# temperature_sensor.net
KiCad netlist of a schematic drawn in EAGLE
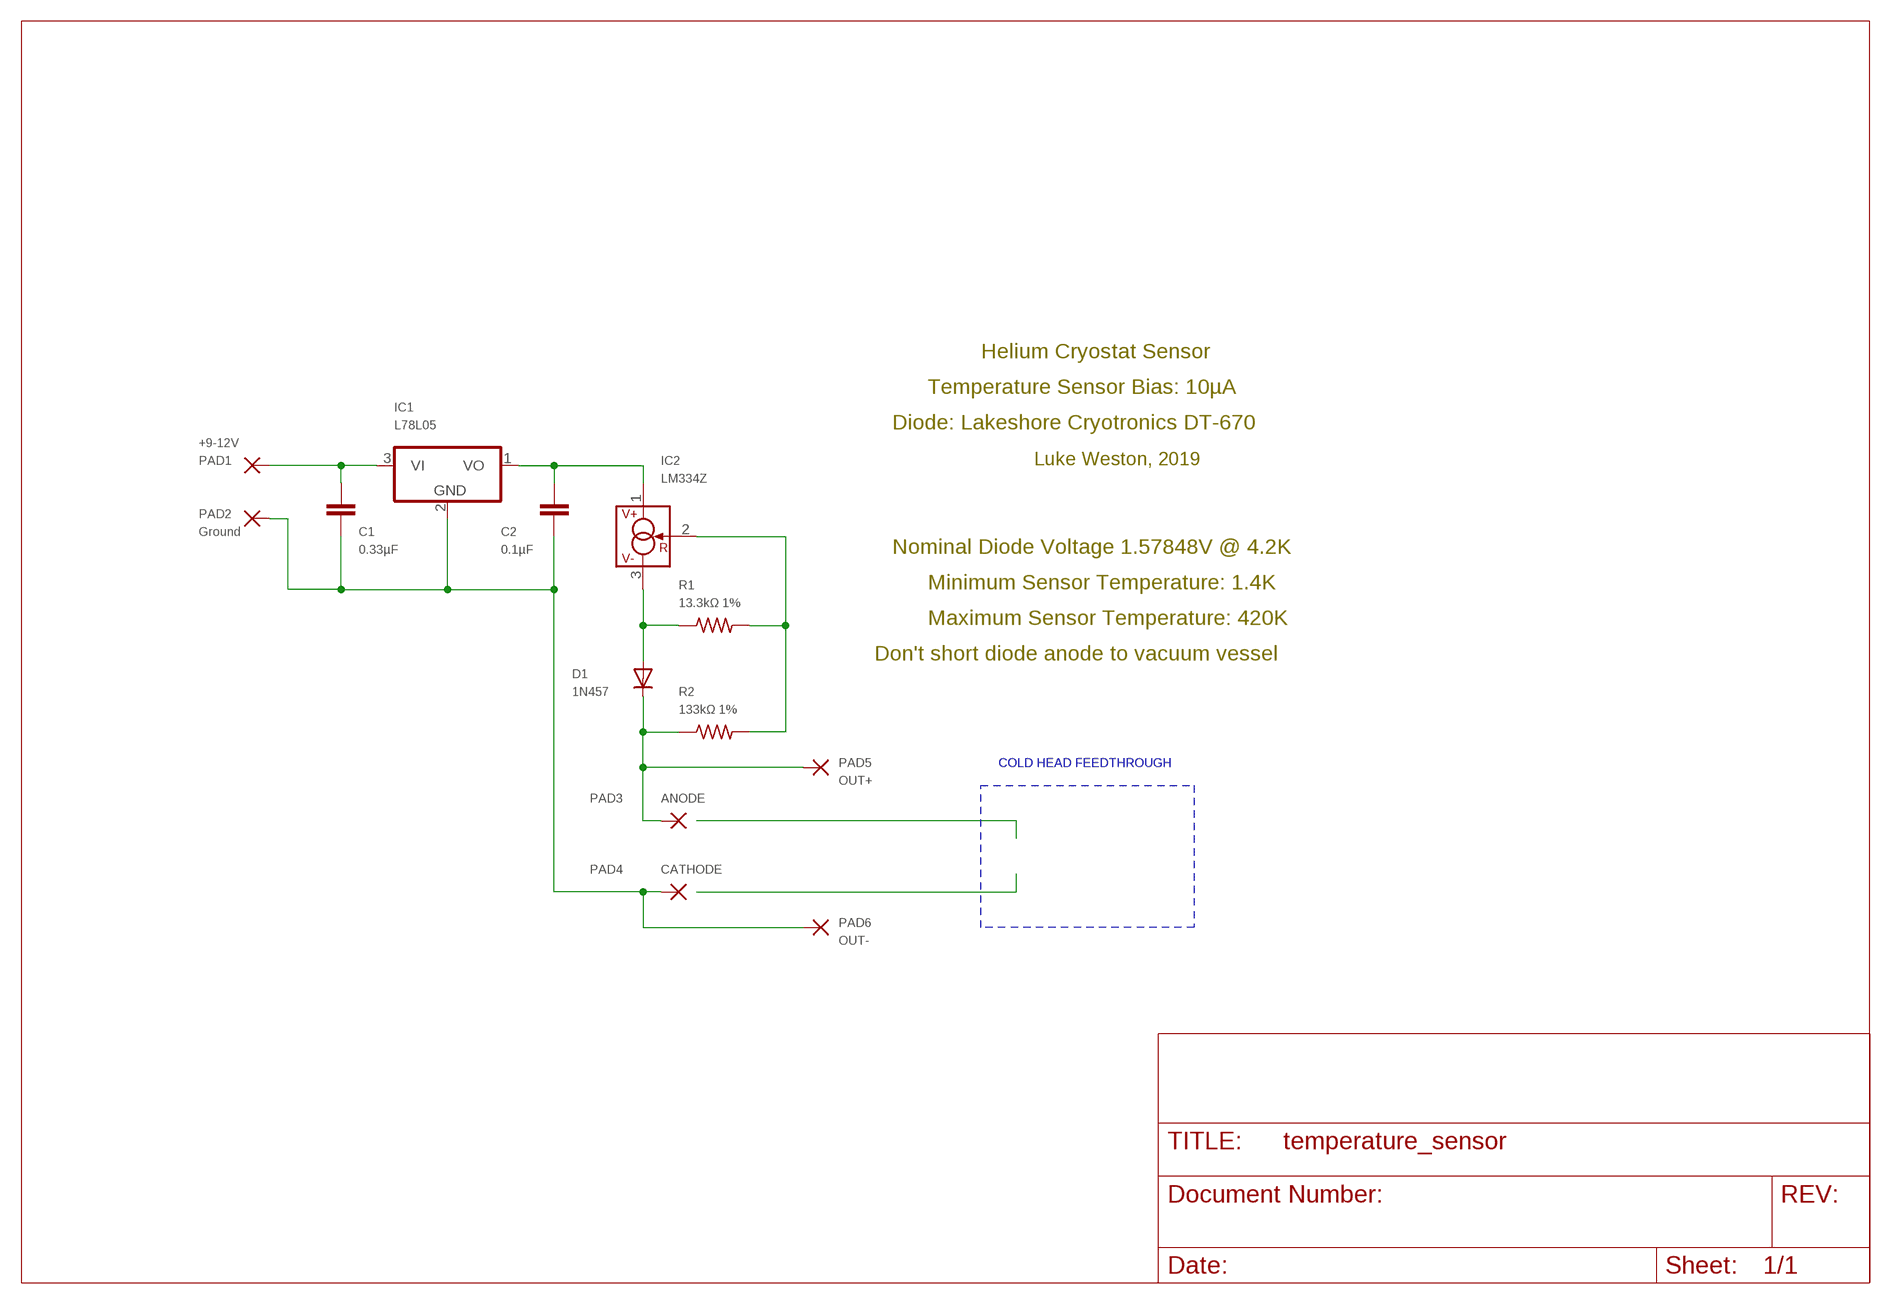
[diagram p0: schematic, sheet 1]

(export (version "E")
  (design (tool "Eeschema 10.0.6"))
  (components
    (comp (ref "C1")
      (value "0.33µF")
      (footprint "eagle-import:C050-024X044")
      (libsource (lib "eagle-import") (part "C-EU050-024X044"))
    )
    (comp (ref "C2")
      (value "0.1µF")
      (footprint "eagle-import:C050-024X044")
      (libsource (lib "eagle-import") (part "C-EU050-024X044"))
    )
    (comp (ref "D1")
      (value "1N457")
      (footprint "eagle-import:DO41-10")
      (libsource (lib "eagle-import") (part "1N4004"))
    )
    (comp (ref "IC1")
      (value "L78L05")
      (footprint "eagle-import:TO92")
      (libsource (lib "eagle-import") (part "78ZL05"))
    )
    (comp (ref "IC2")
      (value "LM334Z")
      (footprint "eagle-import:TO92")
      (libsource (lib "eagle-import") (part "LM34Z3"))
    )
    (comp (ref "PAD1")
      (value "+9-12V")
      (footprint "eagle-import:2,54_1,0")
      (libsource (lib "eagle-import") (part "2,54/1,0"))
    )
    (comp (ref "PAD2")
      (value "Ground")
      (footprint "eagle-import:2,54_1,0")
      (libsource (lib "eagle-import") (part "2,54/1,0"))
    )
    (comp (ref "PAD3")
      (value "ANODE")
      (footprint "eagle-import:2,54_1,0")
      (libsource (lib "eagle-import") (part "2,54/1,0"))
    )
    (comp (ref "PAD4")
      (value "CATHODE")
      (footprint "eagle-import:2,54_1,0")
      (libsource (lib "eagle-import") (part "2,54/1,0"))
    )
    (comp (ref "PAD5")
      (value "OUT+")
      (footprint "eagle-import:2,54_1,0")
      (libsource (lib "eagle-import") (part "2,54/1,0"))
    )
    (comp (ref "PAD6")
      (value "OUT-")
      (footprint "eagle-import:2,54_1,0")
      (libsource (lib "eagle-import") (part "2,54/1,0"))
    )
    (comp (ref "R1")
      (value "13.3kΩ 1%")
      (footprint "eagle-import:0207_10")
      (libsource (lib "eagle-import") (part "R-US_0207/10"))
    )
    (comp (ref "R2")
      (value "133kΩ 1%")
      (footprint "eagle-import:0207_10")
      (libsource (lib "eagle-import") (part "R-US_0207/10"))
    )
  )
  (nets
    (net (code "1") (name "Net-(IC1-GND)") (class "Default")
      (node (ref "C1") (pin "2") (pinfunction "2_2") (pintype "passive"))
      (node (ref "C2") (pin "2") (pinfunction "2_2") (pintype "passive"))
      (node (ref "IC1") (pin "2") (pinfunction "GND_2") (pintype "passive"))
      (node (ref "PAD2") (pin "1") (pinfunction "P_1") (pintype "passive"))
      (node (ref "PAD4") (pin "1") (pinfunction "P_1") (pintype "passive"))
      (node (ref "PAD6") (pin "1") (pinfunction "P_1") (pintype "passive"))
    )
    (net (code "2") (name "Net-(IC1-VI)") (class "Default")
      (node (ref "C1") (pin "1") (pinfunction "1_1") (pintype "passive"))
      (node (ref "IC1") (pin "3") (pinfunction "VI_3") (pintype "input"))
      (node (ref "PAD1") (pin "1") (pinfunction "P_1") (pintype "passive"))
    )
    (net (code "3") (name "Net-(IC1-VO)") (class "Default")
      (node (ref "C2") (pin "1") (pinfunction "1_1") (pintype "passive"))
      (node (ref "IC1") (pin "1") (pinfunction "VO_1") (pintype "passive"))
      (node (ref "IC2") (pin "1") (pinfunction "V+_1") (pintype "passive"))
    )
    (net (code "4") (name "Net-(IC2-R)") (class "Default")
      (node (ref "IC2") (pin "2") (pinfunction "R_2") (pintype "passive"))
      (node (ref "R1") (pin "2") (pinfunction "2_2") (pintype "passive"))
      (node (ref "R2") (pin "2") (pinfunction "2_2") (pintype "passive"))
    )
    (net (code "5") (name "Net-(IC2-V-)") (class "Default")
      (node (ref "D1") (pin "A") (pinfunction "A_A") (pintype "passive"))
      (node (ref "IC2") (pin "3") (pinfunction "V-_3") (pintype "passive"))
      (node (ref "R1") (pin "1") (pinfunction "1_1") (pintype "passive"))
    )
    (net (code "6") (name "Net-(PAD3-P)") (class "Default")
      (node (ref "D1") (pin "C") (pinfunction "C_C") (pintype "passive"))
      (node (ref "PAD3") (pin "1") (pinfunction "P_1") (pintype "passive"))
      (node (ref "PAD5") (pin "1") (pinfunction "P_1") (pintype "passive"))
      (node (ref "R2") (pin "1") (pinfunction "1_1") (pintype "passive"))
    )
  )
)
